# arpie_synch_module.net
KiCad netlist of a schematic drawn in EAGLE
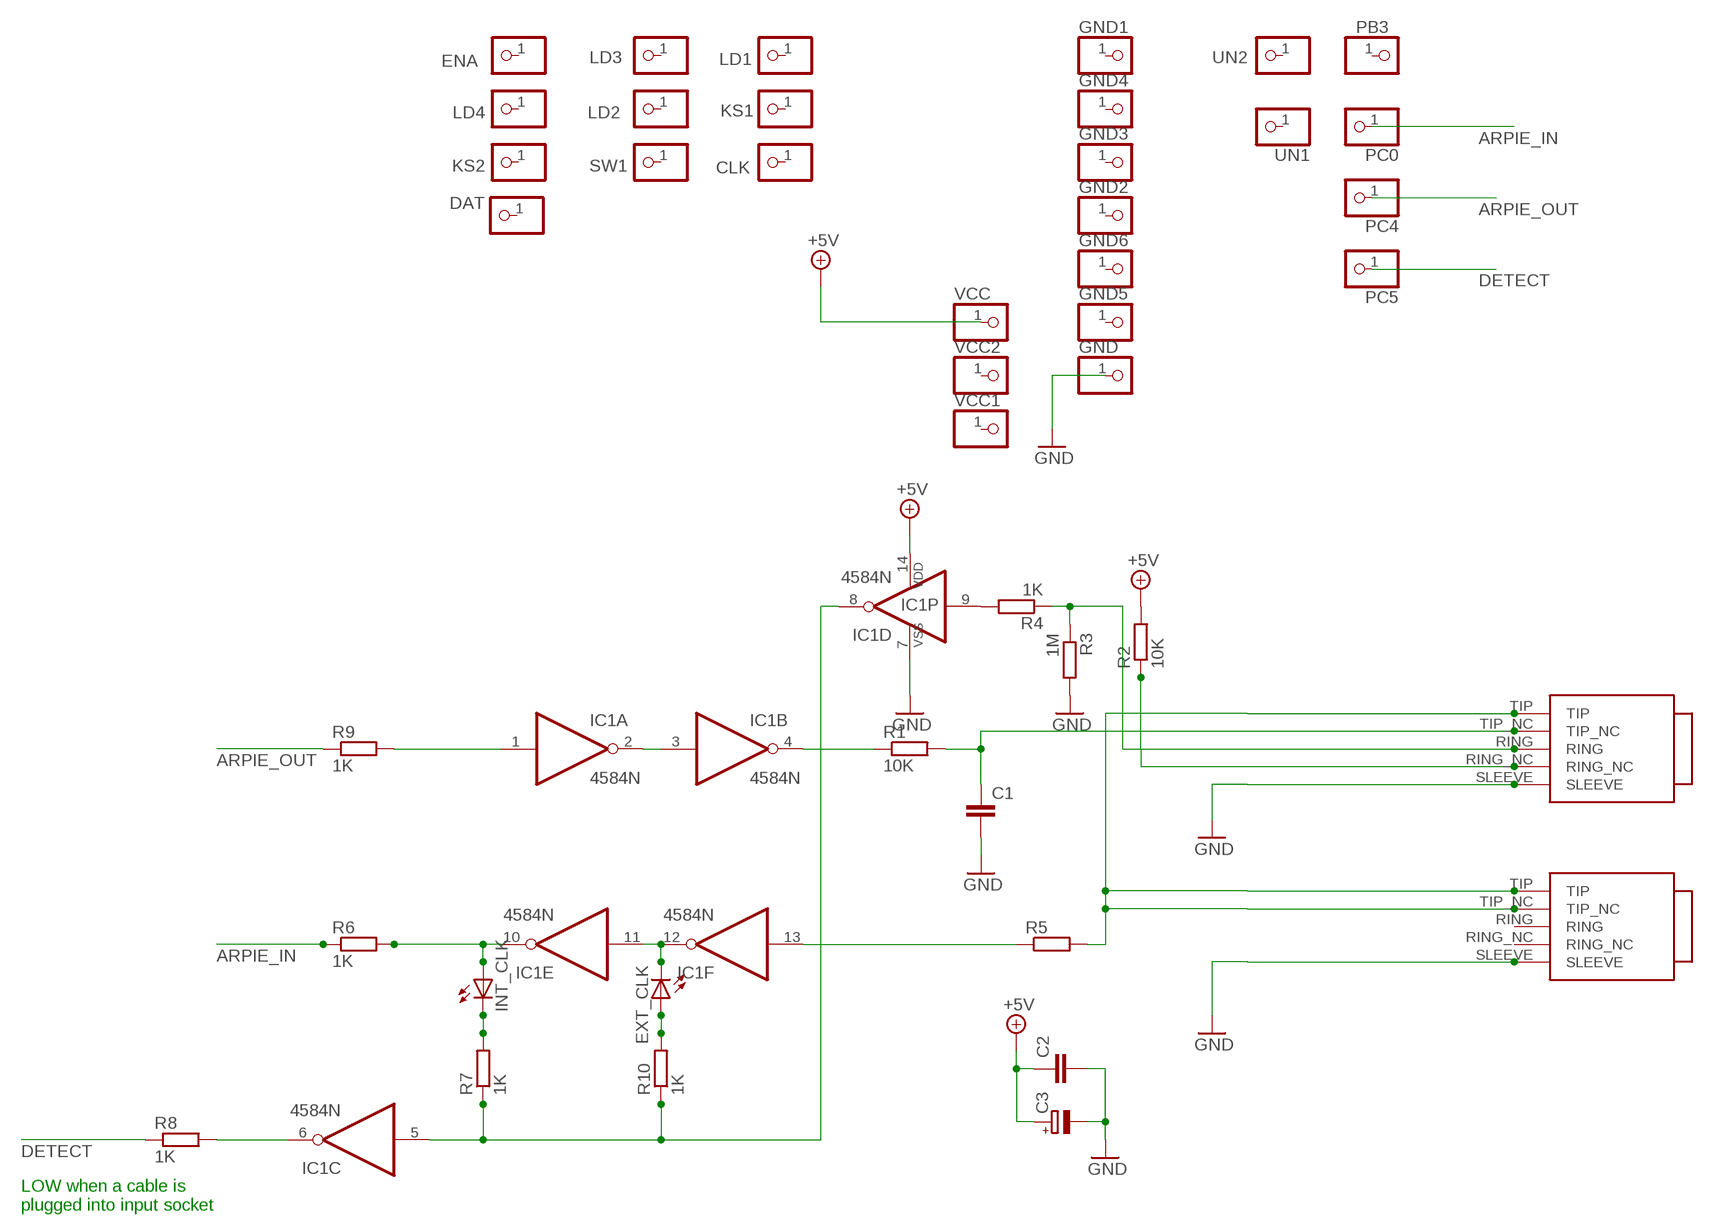
[diagram p0: schematic, sheet 1]

(export (version "E")
  (design (tool "Eeschema 10.0.6"))
  (components
    (comp (ref "C1")
      (value "C-EU025-030X050")
      (footprint "eagle-import:C025-030X050")
      (libsource (lib "eagle-import") (part "C-EU025-030X050"))
    )
    (comp (ref "C2")
      (value "C-EU025-030X050")
      (footprint "eagle-import:C025-030X050")
      (libsource (lib "eagle-import") (part "C-EU025-030X050"))
    )
    (comp (ref "C3")
      (value "CPOL-EUE2-5")
      (footprint "eagle-import:E2-5")
      (libsource (lib "eagle-import") (part "CPOL-EUE2-5"))
    )
    (comp (ref "CLK")
      (value "PINHD-1X1")
      (footprint "eagle-import:1X01")
      (libsource (lib "eagle-import") (part "PINHD-1X1"))
    )
    (comp (ref "DAT")
      (value "PINHD-1X1")
      (footprint "eagle-import:1X01")
      (libsource (lib "eagle-import") (part "PINHD-1X1"))
    )
    (comp (ref "ENA")
      (value "PINHD-1X1")
      (footprint "eagle-import:1X01")
      (libsource (lib "eagle-import") (part "PINHD-1X1"))
    )
    (comp (ref "EXT_CLK")
      (value "LED3MM")
      (footprint "eagle-import:LED3MM")
      (libsource (lib "eagle-import") (part "LED3MM"))
    )
    (comp (ref "GND")
      (value "PINHD-1X1")
      (footprint "eagle-import:1X01")
      (libsource (lib "eagle-import") (part "PINHD-1X1"))
    )
    (comp (ref "GND1")
      (value "PINHD-1X1")
      (footprint "eagle-import:1X01")
      (libsource (lib "eagle-import") (part "PINHD-1X1"))
    )
    (comp (ref "GND2")
      (value "PINHD-1X1")
      (footprint "eagle-import:1X01")
      (libsource (lib "eagle-import") (part "PINHD-1X1"))
    )
    (comp (ref "GND3")
      (value "PINHD-1X1")
      (footprint "eagle-import:1X01")
      (libsource (lib "eagle-import") (part "PINHD-1X1"))
    )
    (comp (ref "GND4")
      (value "PINHD-1X1")
      (footprint "eagle-import:1X01")
      (libsource (lib "eagle-import") (part "PINHD-1X1"))
    )
    (comp (ref "GND5")
      (value "PINHD-1X1")
      (footprint "eagle-import:1X01")
      (libsource (lib "eagle-import") (part "PINHD-1X1"))
    )
    (comp (ref "GND6")
      (value "PINHD-1X1")
      (footprint "eagle-import:1X01")
      (libsource (lib "eagle-import") (part "PINHD-1X1"))
    )
    (comp (ref "IC1")
      (value "4584N")
      (footprint "eagle-import:DIL14")
      (libsource (lib "eagle-import") (part "4584N"))
    )
    (comp (ref "INT_CLK")
      (value "LED3MM")
      (footprint "eagle-import:LED3MM")
      (libsource (lib "eagle-import") (part "LED3MM"))
    )
    (comp (ref "KS1")
      (value "PINHD-1X1")
      (footprint "eagle-import:1X01")
      (libsource (lib "eagle-import") (part "PINHD-1X1"))
    )
    (comp (ref "KS2")
      (value "PINHD-1X1")
      (footprint "eagle-import:1X01")
      (libsource (lib "eagle-import") (part "PINHD-1X1"))
    )
    (comp (ref "LD1")
      (value "PINHD-1X1")
      (footprint "eagle-import:1X01")
      (libsource (lib "eagle-import") (part "PINHD-1X1"))
    )
    (comp (ref "LD2")
      (value "PINHD-1X1")
      (footprint "eagle-import:1X01")
      (libsource (lib "eagle-import") (part "PINHD-1X1"))
    )
    (comp (ref "LD3")
      (value "PINHD-1X1")
      (footprint "eagle-import:1X01")
      (libsource (lib "eagle-import") (part "PINHD-1X1"))
    )
    (comp (ref "LD4")
      (value "PINHD-1X1")
      (footprint "eagle-import:1X01")
      (libsource (lib "eagle-import") (part "PINHD-1X1"))
    )
    (comp (ref "PB3")
      (value "PINHD-1X1")
      (footprint "eagle-import:1X01")
      (libsource (lib "eagle-import") (part "PINHD-1X1"))
    )
    (comp (ref "PC0")
      (value "PINHD-1X1")
      (footprint "eagle-import:1X01")
      (libsource (lib "eagle-import") (part "PINHD-1X1"))
    )
    (comp (ref "PC4")
      (value "PINHD-1X1")
      (footprint "eagle-import:1X01")
      (libsource (lib "eagle-import") (part "PINHD-1X1"))
    )
    (comp (ref "PC5")
      (value "PINHD-1X1")
      (footprint "eagle-import:1X01")
      (libsource (lib "eagle-import") (part "PINHD-1X1"))
    )
    (comp (ref "R1")
      (value "10K")
      (footprint "eagle-import:0207_7")
      (libsource (lib "eagle-import") (part "R-EU_0207/7"))
    )
    (comp (ref "R2")
      (value "10K")
      (footprint "eagle-import:0207_7")
      (libsource (lib "eagle-import") (part "R-EU_0207/7"))
    )
    (comp (ref "R3")
      (value "1M")
      (footprint "eagle-import:0207_7")
      (libsource (lib "eagle-import") (part "R-EU_0207/7"))
    )
    (comp (ref "R4")
      (value "1K")
      (footprint "eagle-import:0207_7")
      (libsource (lib "eagle-import") (part "R-EU_0207/7"))
    )
    (comp (ref "R5")
      (value "R-EU_0207/7")
      (footprint "eagle-import:0207_7")
      (libsource (lib "eagle-import") (part "R-EU_0207/7"))
    )
    (comp (ref "R6")
      (value "1K")
      (footprint "eagle-import:0207_7")
      (libsource (lib "eagle-import") (part "R-EU_0207/7"))
    )
    (comp (ref "R7")
      (value "1K")
      (footprint "eagle-import:0207_7")
      (libsource (lib "eagle-import") (part "R-EU_0207/7"))
    )
    (comp (ref "R8")
      (value "1K")
      (footprint "eagle-import:0207_7")
      (libsource (lib "eagle-import") (part "R-EU_0207/7"))
    )
    (comp (ref "R9")
      (value "1K")
      (footprint "eagle-import:0207_7")
      (libsource (lib "eagle-import") (part "R-EU_0207/7"))
    )
    (comp (ref "R10")
      (value "1K")
      (footprint "eagle-import:0207_7")
      (libsource (lib "eagle-import") (part "R-EU_0207/7"))
    )
    (comp (ref "SW1")
      (value "PINHD-1X1")
      (footprint "eagle-import:1X01")
      (libsource (lib "eagle-import") (part "PINHD-1X1"))
    )
    (comp (ref "U$1")
      (value "TRUCONNECTJACK")
      (footprint "eagle-import:TRUCONNECTJACK")
      (libsource (lib "eagle-import") (part "TRUCONNECTJACK"))
    )
    (comp (ref "U$2")
      (value "TRUCONNECTJACK")
      (footprint "eagle-import:TRUCONNECTJACK")
      (libsource (lib "eagle-import") (part "TRUCONNECTJACK"))
    )
    (comp (ref "UN1")
      (value "PINHD-1X1")
      (footprint "eagle-import:1X01")
      (libsource (lib "eagle-import") (part "PINHD-1X1"))
    )
    (comp (ref "UN2")
      (value "PINHD-1X1")
      (footprint "eagle-import:1X01")
      (libsource (lib "eagle-import") (part "PINHD-1X1"))
    )
    (comp (ref "VCC")
      (value "PINHD-1X1")
      (footprint "eagle-import:1X01")
      (libsource (lib "eagle-import") (part "PINHD-1X1"))
    )
    (comp (ref "VCC1")
      (value "PINHD-1X1")
      (footprint "eagle-import:1X01")
      (libsource (lib "eagle-import") (part "PINHD-1X1"))
    )
    (comp (ref "VCC2")
      (value "PINHD-1X1")
      (footprint "eagle-import:1X01")
      (libsource (lib "eagle-import") (part "PINHD-1X1"))
    )
  )
  (nets
    (net (code "1") (name "+5V") (class "Default")
      (node (ref "C2") (pin "1") (pinfunction "1_1") (pintype "passive"))
      (node (ref "C3") (pin "+") (pinfunction "+_+") (pintype "passive"))
      (node (ref "IC1") (pin "14") (pinfunction "VDD_14") (pintype "power_in"))
      (node (ref "R2") (pin "2") (pinfunction "2_2") (pintype "passive"))
      (node (ref "VCC") (pin "1") (pinfunction "1_1") (pintype "passive"))
    )
    (net (code "2") (name "/ARPIE_IN") (class "Default")
      (node (ref "PC0") (pin "1") (pinfunction "1_1") (pintype "passive"))
      (node (ref "R6") (pin "1") (pinfunction "1_1") (pintype "passive"))
    )
    (net (code "3") (name "/ARPIE_OUT") (class "Default")
      (node (ref "PC4") (pin "1") (pinfunction "1_1") (pintype "passive"))
      (node (ref "R9") (pin "1") (pinfunction "1_1") (pintype "passive"))
    )
    (net (code "4") (name "/DETECT") (class "Default")
      (node (ref "PC5") (pin "1") (pinfunction "1_1") (pintype "passive"))
      (node (ref "R8") (pin "1") (pinfunction "1_1") (pintype "passive"))
    )
    (net (code "5") (name "GND") (class "Default")
      (node (ref "C1") (pin "2") (pinfunction "2_2") (pintype "passive"))
      (node (ref "C2") (pin "2") (pinfunction "2_2") (pintype "passive"))
      (node (ref "C3") (pin "-") (pinfunction "-_-") (pintype "passive"))
      (node (ref "GND") (pin "1") (pinfunction "1_1") (pintype "passive"))
      (node (ref "IC1") (pin "7") (pinfunction "VSS_7") (pintype "power_in"))
      (node (ref "R3") (pin "2") (pinfunction "2_2") (pintype "passive"))
      (node (ref "U$1") (pin "SLEEVE") (pinfunction "SLEEVE_SLEEVE") (pintype "bidirectional"))
      (node (ref "U$2") (pin "SLEEVE") (pinfunction "SLEEVE_SLEEVE") (pintype "bidirectional"))
    )
    (net (code "6") (name "Net-(C1-Pad1)") (class "Default")
      (node (ref "C1") (pin "1") (pinfunction "1_1") (pintype "passive"))
      (node (ref "R1") (pin "2") (pinfunction "2_2") (pintype "passive"))
      (node (ref "U$1") (pin "TIP_NC") (pinfunction "TIP_NC_TIP_NC") (pintype "bidirectional"))
    )
    (net (code "7") (name "Net-(EXT_CLK-C)") (class "Default")
      (node (ref "EXT_CLK") (pin "K") (pinfunction "C_K") (pintype "passive"))
      (node (ref "IC1") (pin "11") (pinfunction "I_11") (pintype "input"))
      (node (ref "IC1") (pin "12") (pinfunction "O_12") (pintype "output"))
    )
    (net (code "8") (name "Net-(EXT_CLK-PadA)") (class "Default")
      (node (ref "EXT_CLK") (pin "A") (pinfunction "A_A") (pintype "passive"))
      (node (ref "R10") (pin "2") (pinfunction "2_2") (pintype "passive"))
    )
    (net (code "9") (name "Net-(IC1A-I)") (class "Default")
      (node (ref "IC1") (pin "1") (pinfunction "I_1") (pintype "input"))
      (node (ref "R9") (pin "2") (pinfunction "2_2") (pintype "passive"))
    )
    (net (code "10") (name "Net-(IC1A-O)") (class "Default")
      (node (ref "IC1") (pin "2") (pinfunction "O_2") (pintype "output"))
      (node (ref "IC1") (pin "3") (pinfunction "I_3") (pintype "input"))
    )
    (net (code "11") (name "Net-(IC1B-O)") (class "Default")
      (node (ref "IC1") (pin "4") (pinfunction "O_4") (pintype "output"))
      (node (ref "R1") (pin "1") (pinfunction "1_1") (pintype "passive"))
    )
    (net (code "12") (name "Net-(IC1C-I)") (class "Default")
      (node (ref "IC1") (pin "5") (pinfunction "I_5") (pintype "input"))
      (node (ref "IC1") (pin "8") (pinfunction "O_8") (pintype "output"))
      (node (ref "R10") (pin "1") (pinfunction "1_1") (pintype "passive"))
      (node (ref "R7") (pin "1") (pinfunction "1_1") (pintype "passive"))
    )
    (net (code "13") (name "Net-(IC1C-O)") (class "Default")
      (node (ref "IC1") (pin "6") (pinfunction "O_6") (pintype "output"))
      (node (ref "R8") (pin "2") (pinfunction "2_2") (pintype "passive"))
    )
    (net (code "14") (name "Net-(IC1D-I)") (class "Default")
      (node (ref "IC1") (pin "9") (pinfunction "I_9") (pintype "input"))
      (node (ref "R4") (pin "2") (pinfunction "2_2") (pintype "passive"))
    )
    (net (code "15") (name "Net-(IC1E-O)") (class "Default")
      (node (ref "IC1") (pin "10") (pinfunction "O_10") (pintype "output"))
      (node (ref "INT_CLK") (pin "A") (pinfunction "A_A") (pintype "passive"))
      (node (ref "R6") (pin "2") (pinfunction "2_2") (pintype "passive"))
    )
    (net (code "16") (name "Net-(IC1F-I)") (class "Default")
      (node (ref "IC1") (pin "13") (pinfunction "I_13") (pintype "input"))
      (node (ref "R5") (pin "1") (pinfunction "1_1") (pintype "passive"))
    )
    (net (code "17") (name "Net-(INT_CLK-C)") (class "Default")
      (node (ref "INT_CLK") (pin "K") (pinfunction "C_K") (pintype "passive"))
      (node (ref "R7") (pin "2") (pinfunction "2_2") (pintype "passive"))
    )
    (net (code "18") (name "Net-(R2-Pad1)") (class "Default")
      (node (ref "R2") (pin "1") (pinfunction "1_1") (pintype "passive"))
      (node (ref "U$1") (pin "RING_NC") (pinfunction "RING_NC_RING_NC") (pintype "bidirectional"))
    )
    (net (code "19") (name "Net-(R3-Pad1)") (class "Default")
      (node (ref "R3") (pin "1") (pinfunction "1_1") (pintype "passive"))
      (node (ref "R4") (pin "1") (pinfunction "1_1") (pintype "passive"))
      (node (ref "U$1") (pin "RING") (pinfunction "RING_RING") (pintype "bidirectional"))
    )
    (net (code "20") (name "Net-(R5-Pad2)") (class "Default")
      (node (ref "R5") (pin "2") (pinfunction "2_2") (pintype "passive"))
      (node (ref "U$1") (pin "TIP") (pinfunction "TIP_TIP") (pintype "bidirectional"))
      (node (ref "U$2") (pin "TIP") (pinfunction "TIP_TIP") (pintype "bidirectional"))
      (node (ref "U$2") (pin "TIP_NC") (pinfunction "TIP_NC_TIP_NC") (pintype "bidirectional"))
    )
    (net (code "21") (name "unconnected-(CLK-Pad1)") (class "Default")
      (node (ref "CLK") (pin "1") (pinfunction "1_1") (pintype "passive"))
    )
    (net (code "22") (name "unconnected-(DAT-Pad1)") (class "Default")
      (node (ref "DAT") (pin "1") (pinfunction "1_1") (pintype "passive"))
    )
    (net (code "23") (name "unconnected-(ENA-Pad1)") (class "Default")
      (node (ref "ENA") (pin "1") (pinfunction "1_1") (pintype "passive"))
    )
    (net (code "24") (name "unconnected-(GND1-Pad1)") (class "Default")
      (node (ref "GND1") (pin "1") (pinfunction "1_1") (pintype "passive"))
    )
    (net (code "25") (name "unconnected-(GND2-Pad1)") (class "Default")
      (node (ref "GND2") (pin "1") (pinfunction "1_1") (pintype "passive"))
    )
    (net (code "26") (name "unconnected-(GND3-Pad1)") (class "Default")
      (node (ref "GND3") (pin "1") (pinfunction "1_1") (pintype "passive"))
    )
    (net (code "27") (name "unconnected-(GND4-Pad1)") (class "Default")
      (node (ref "GND4") (pin "1") (pinfunction "1_1") (pintype "passive"))
    )
    (net (code "28") (name "unconnected-(GND5-Pad1)") (class "Default")
      (node (ref "GND5") (pin "1") (pinfunction "1_1") (pintype "passive"))
    )
    (net (code "29") (name "unconnected-(GND6-Pad1)") (class "Default")
      (node (ref "GND6") (pin "1") (pinfunction "1_1") (pintype "passive"))
    )
    (net (code "30") (name "unconnected-(KS1-Pad1)") (class "Default")
      (node (ref "KS1") (pin "1") (pinfunction "1_1") (pintype "passive"))
    )
    (net (code "31") (name "unconnected-(KS2-Pad1)") (class "Default")
      (node (ref "KS2") (pin "1") (pinfunction "1_1") (pintype "passive"))
    )
    (net (code "32") (name "unconnected-(LD1-Pad1)") (class "Default")
      (node (ref "LD1") (pin "1") (pinfunction "1_1") (pintype "passive"))
    )
    (net (code "33") (name "unconnected-(LD2-Pad1)") (class "Default")
      (node (ref "LD2") (pin "1") (pinfunction "1_1") (pintype "passive"))
    )
    (net (code "34") (name "unconnected-(LD3-Pad1)") (class "Default")
      (node (ref "LD3") (pin "1") (pinfunction "1_1") (pintype "passive"))
    )
    (net (code "35") (name "unconnected-(LD4-Pad1)") (class "Default")
      (node (ref "LD4") (pin "1") (pinfunction "1_1") (pintype "passive"))
    )
    (net (code "36") (name "unconnected-(PB3-Pad1)") (class "Default")
      (node (ref "PB3") (pin "1") (pinfunction "1_1") (pintype "passive"))
    )
    (net (code "37") (name "unconnected-(SW1-Pad1)") (class "Default")
      (node (ref "SW1") (pin "1") (pinfunction "1_1") (pintype "passive"))
    )
    (net (code "38") (name "unconnected-(U$2-PadRING)") (class "Default")
      (node (ref "U$2") (pin "RING") (pinfunction "RING_RING") (pintype "bidirectional"))
    )
    (net (code "39") (name "unconnected-(U$2-PadRING_NC)") (class "Default")
      (node (ref "U$2") (pin "RING_NC") (pinfunction "RING_NC_RING_NC") (pintype "bidirectional"))
    )
    (net (code "40") (name "unconnected-(UN1-Pad1)") (class "Default")
      (node (ref "UN1") (pin "1") (pinfunction "1_1") (pintype "passive"))
    )
    (net (code "41") (name "unconnected-(UN2-Pad1)") (class "Default")
      (node (ref "UN2") (pin "1") (pinfunction "1_1") (pintype "passive"))
    )
    (net (code "42") (name "unconnected-(VCC1-Pad1)") (class "Default")
      (node (ref "VCC1") (pin "1") (pinfunction "1_1") (pintype "passive"))
    )
    (net (code "43") (name "unconnected-(VCC2-Pad1)") (class "Default")
      (node (ref "VCC2") (pin "1") (pinfunction "1_1") (pintype "passive"))
    )
  )
)
